# ADC_ADC084S021_SPI.net
KiCad netlist of a schematic drawn in Altium Designer
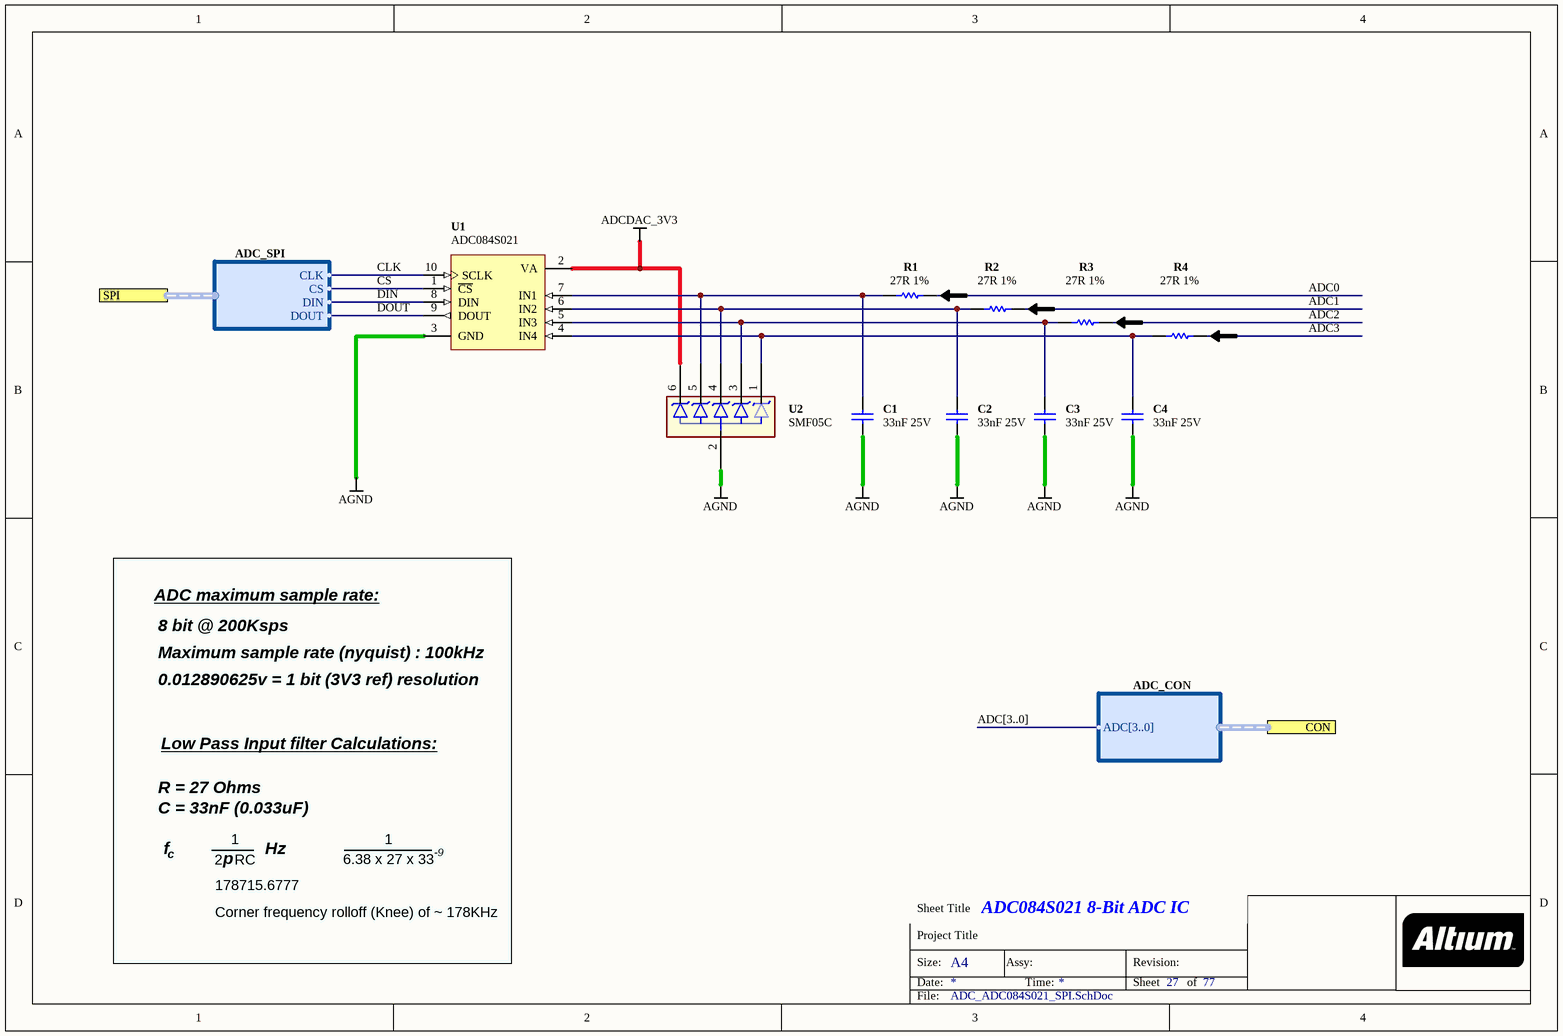
[diagram p0: ADC_ADC084S021_SPI.SchDoc]

(export (version "E")
  (design (tool "Eeschema 10.0.6"))
  (components
    (comp (ref "C1")
      (value "33nF 25V")
      (footprint "CAPC1005-STAR")
      (description "Capacitor, Ceramic, 33nF 10% 25V 0402 (1005) X7R")
      (fields (field (name "TOLERANCE") "10 %"))
      (libsource (lib "AltiumDesignLibrary") (part "CAP-NP"))
    )
    (comp (ref "C2")
      (value "33nF 25V")
      (footprint "CAPC1005-STAR")
      (description "Capacitor, Ceramic, 33nF 10% 25V 0402 (1005) X7R")
      (fields (field (name "TOLERANCE") "10 %"))
      (libsource (lib "AltiumDesignLibrary") (part "CAP-NP"))
    )
    (comp (ref "C3")
      (value "33nF 25V")
      (footprint "CAPC1005-STAR")
      (description "Capacitor, Ceramic, 33nF 10% 25V 0402 (1005) X7R")
      (fields (field (name "TOLERANCE") "10 %"))
      (libsource (lib "AltiumDesignLibrary") (part "CAP-NP"))
    )
    (comp (ref "C4")
      (value "33nF 25V")
      (footprint "CAPC1005-STAR")
      (description "Capacitor, Ceramic, 33nF 10% 25V 0402 (1005) X7R")
      (fields (field (name "TOLERANCE") "10 %"))
      (libsource (lib "AltiumDesignLibrary") (part "CAP-NP"))
    )
    (comp (ref "R1")
      (value "27R 1%")
      (footprint "RESC1005-STAR")
      (description "Resistor, 27R 1% 0402 (1005)")
      (fields (field (name "TOLERANCE") "1 %"))
      (libsource (lib "AltiumDesignLibrary") (part "RES"))
    )
    (comp (ref "R2")
      (value "27R 1%")
      (footprint "RESC1005-STAR")
      (description "Resistor, 27R 1% 0402 (1005)")
      (fields (field (name "TOLERANCE") "1 %"))
      (libsource (lib "AltiumDesignLibrary") (part "RES"))
    )
    (comp (ref "R3")
      (value "27R 1%")
      (footprint "RESC1005-STAR")
      (description "Resistor, 27R 1% 0402 (1005)")
      (fields (field (name "TOLERANCE") "1 %"))
      (libsource (lib "AltiumDesignLibrary") (part "RES"))
    )
    (comp (ref "R4")
      (value "27R 1%")
      (footprint "RESC1005-STAR")
      (description "Resistor, 27R 1% 0402 (1005)")
      (fields (field (name "TOLERANCE") "1 %"))
      (libsource (lib "AltiumDesignLibrary") (part "RES"))
    )
    (comp (ref "U1")
      (value "ADC084S021")
      (footprint "TSSOP50P490-10AN")
      (description "ADC084S021, 8-bit ADC, 4 Channel, 50 ksps to 200ksps, SPI")
      (libsource (lib "AltiumDesignLibrary") (part "ADC084S021"))
    )
    (comp (ref "U2")
      (value "SMF05C")
      (footprint "SC70_6L")
      (description "TVS Diode Array  For ESD and Latch-Up Protection")
      (libsource (lib "AltiumDesignLibrary") (part "SMF05C"))
    )
  )
  (nets
    (net (code "3") (name "/ADC0") (class "Default")
      (node (ref "R1") (pin "1") (pinfunction "1_1") (pintype "passive"))
    )
    (net (code "4") (name "/ADC1") (class "Default")
      (node (ref "R2") (pin "1") (pinfunction "1_1") (pintype "passive"))
    )
    (net (code "5") (name "/ADC2") (class "Default")
      (node (ref "R3") (pin "1") (pinfunction "1_1") (pintype "passive"))
    )
    (net (code "6") (name "/ADC3") (class "Default")
      (node (ref "R4") (pin "1") (pinfunction "1_1") (pintype "passive"))
    )
    (net (code "8") (name "/CLK") (class "Default")
      (node (ref "U1") (pin "10") (pinfunction "SCLK_10") (pintype "input"))
    )
    (net (code "9") (name "/CS") (class "Default")
      (node (ref "U1") (pin "1") (pinfunction "~{CS}_1") (pintype "input"))
    )
    (net (code "10") (name "/DIN") (class "Default")
      (node (ref "U1") (pin "8") (pinfunction "DIN_8") (pintype "input"))
    )
    (net (code "11") (name "/DOUT") (class "Default")
      (node (ref "U1") (pin "9") (pinfunction "DOUT_9") (pintype "output"))
    )
    (net (code "14") (name "ADCDAC_3V3") (class "Default")
      (node (ref "U1") (pin "2") (pinfunction "VA_2") (pintype "power_in"))
      (node (ref "U2") (pin "6") (pinfunction "6_6") (pintype "passive"))
    )
    (net (code "15") (name "AGND") (class "Default")
      (node (ref "C1") (pin "2") (pinfunction "2_2") (pintype "passive"))
      (node (ref "C2") (pin "2") (pinfunction "2_2") (pintype "passive"))
      (node (ref "C3") (pin "2") (pinfunction "2_2") (pintype "passive"))
      (node (ref "C4") (pin "2") (pinfunction "2_2") (pintype "passive"))
      (node (ref "U1") (pin "3") (pinfunction "GND_3") (pintype "power_in"))
      (node (ref "U2") (pin "2") (pinfunction "2_2") (pintype "passive"))
    )
    (net (code "16") (name "Net-(U1-IN1)") (class "Default")
      (node (ref "C1") (pin "1") (pinfunction "1_1") (pintype "passive"))
      (node (ref "R1") (pin "2") (pinfunction "2_2") (pintype "passive"))
      (node (ref "U1") (pin "7") (pinfunction "IN1_7") (pintype "input"))
      (node (ref "U2") (pin "5") (pinfunction "5_5") (pintype "passive"))
    )
    (net (code "17") (name "Net-(U1-IN2)") (class "Default")
      (node (ref "C2") (pin "1") (pinfunction "1_1") (pintype "passive"))
      (node (ref "R2") (pin "2") (pinfunction "2_2") (pintype "passive"))
      (node (ref "U1") (pin "6") (pinfunction "IN2_6") (pintype "input"))
      (node (ref "U2") (pin "4") (pinfunction "4_4") (pintype "passive"))
    )
    (net (code "18") (name "Net-(U1-IN3)") (class "Default")
      (node (ref "C3") (pin "1") (pinfunction "1_1") (pintype "passive"))
      (node (ref "R3") (pin "2") (pinfunction "2_2") (pintype "passive"))
      (node (ref "U1") (pin "5") (pinfunction "IN3_5") (pintype "input"))
      (node (ref "U2") (pin "3") (pinfunction "3_3") (pintype "passive"))
    )
    (net (code "19") (name "Net-(U1-IN4)") (class "Default")
      (node (ref "C4") (pin "1") (pinfunction "1_1") (pintype "passive"))
      (node (ref "R4") (pin "2") (pinfunction "2_2") (pintype "passive"))
      (node (ref "U1") (pin "4") (pinfunction "IN4_4") (pintype "input"))
      (node (ref "U2") (pin "1") (pinfunction "1_1") (pintype "passive"))
    )
  )
)
